# rf-power-detector.net
KiCad netlist of a schematic drawn in EAGLE
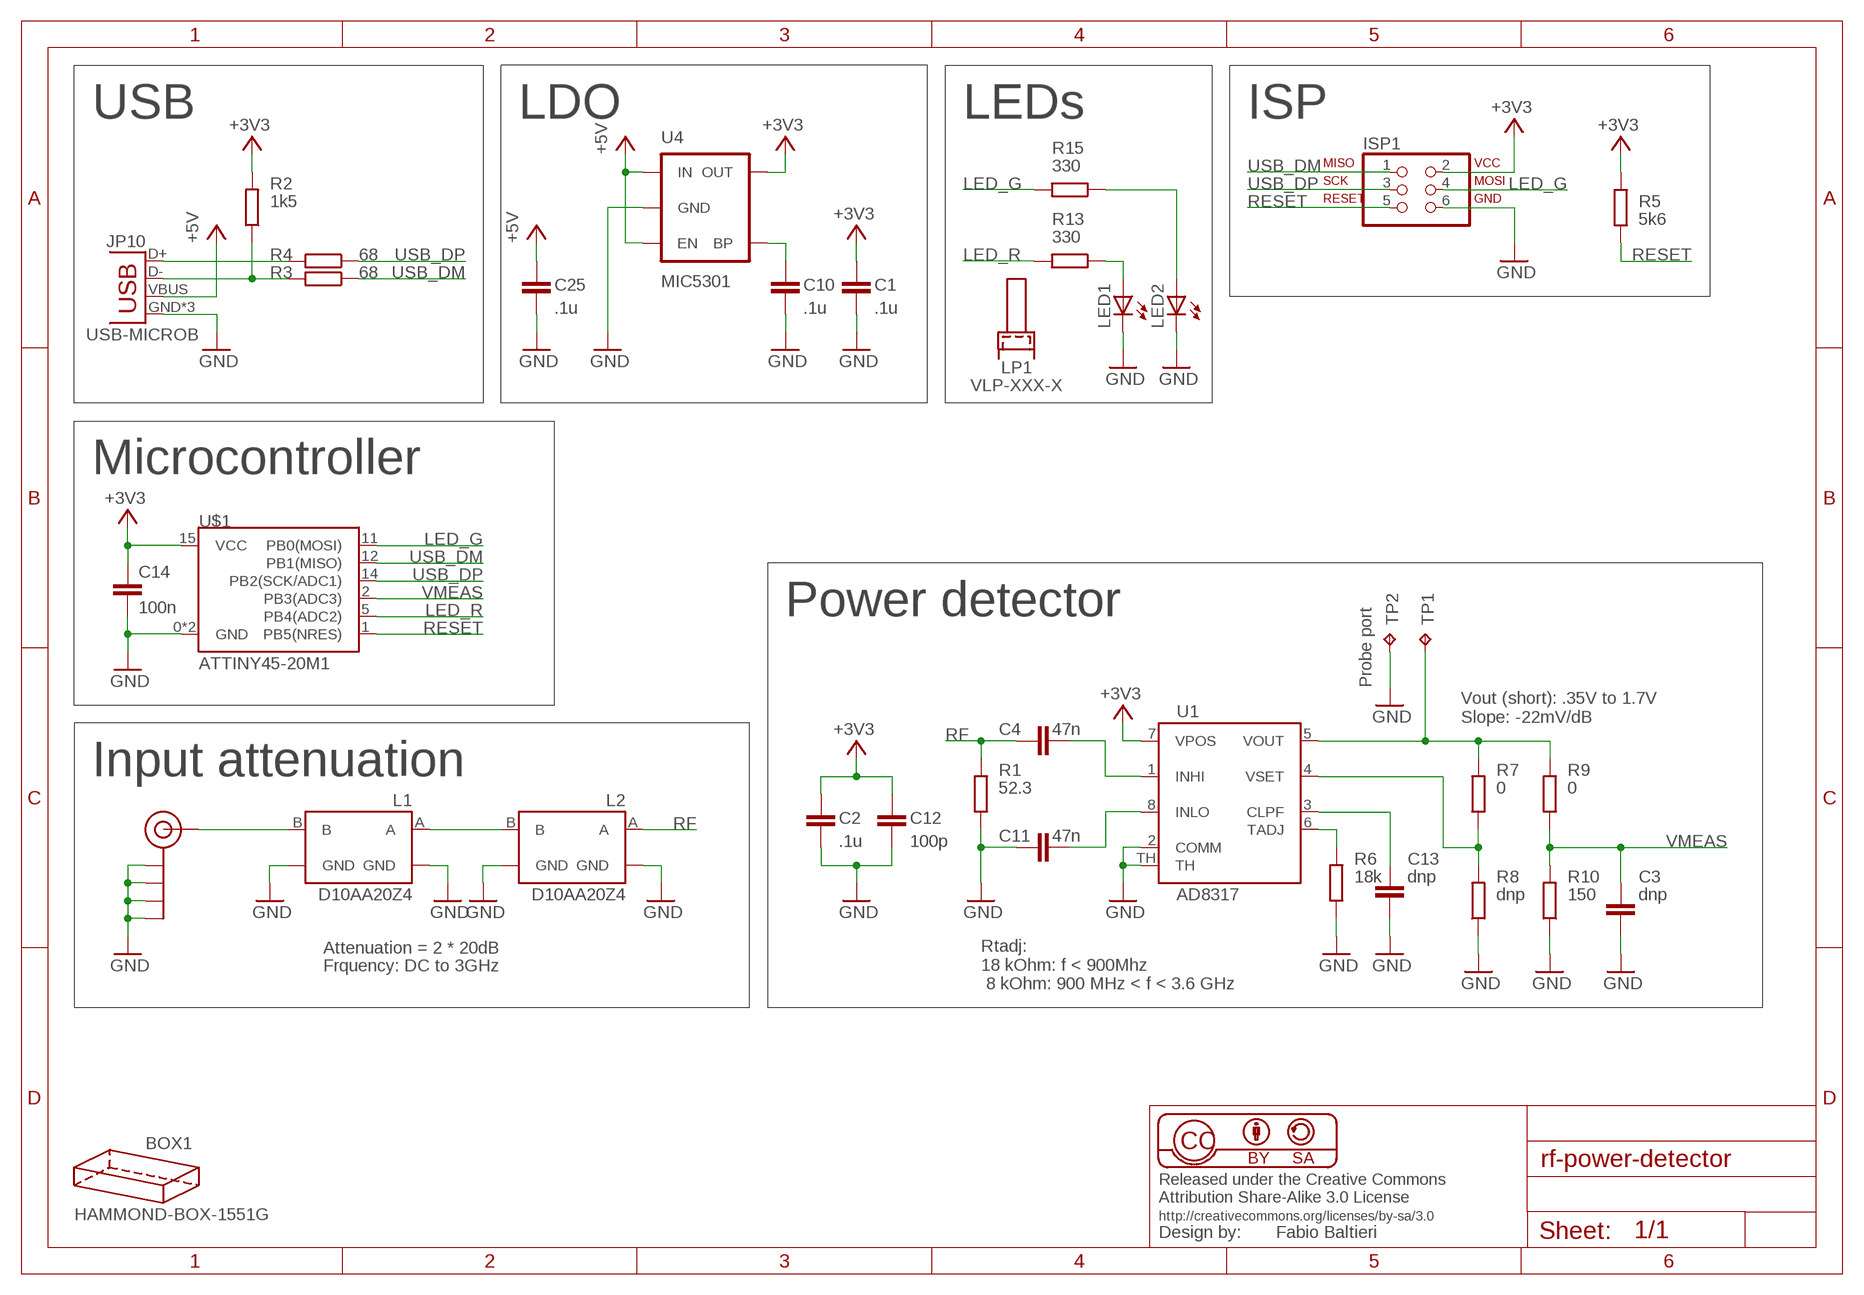
[diagram p0: schematic, sheet 1]

(export (version "E")
  (design (tool "Eeschema 10.0.6"))
  (components
    (comp (ref "BOX1")
      (value "HAMMOND-BOX-1551G")
      (footprint "eagle-import:1551G")
      (libsource (lib "eagle-import") (part "HAMMOND-BOX-1551G"))
    )
    (comp (ref "C1")
      (value ".1u")
      (footprint "eagle-import:C0603")
      (libsource (lib "eagle-import") (part "C-EUC0603"))
    )
    (comp (ref "C2")
      (value ".1u")
      (footprint "eagle-import:C0603")
      (libsource (lib "eagle-import") (part "C-EUC0603"))
    )
    (comp (ref "C3")
      (value "dnp")
      (footprint "eagle-import:C0603")
      (libsource (lib "eagle-import") (part "C-EUC0603"))
    )
    (comp (ref "C4")
      (value "47n")
      (footprint "eagle-import:C0603")
      (libsource (lib "eagle-import") (part "C-EUC0603"))
    )
    (comp (ref "C10")
      (value ".1u")
      (footprint "eagle-import:C0603")
      (libsource (lib "eagle-import") (part "C-EUC0603"))
    )
    (comp (ref "C11")
      (value "47n")
      (footprint "eagle-import:C0603")
      (libsource (lib "eagle-import") (part "C-EUC0603"))
    )
    (comp (ref "C12")
      (value "100p")
      (footprint "eagle-import:C0603")
      (libsource (lib "eagle-import") (part "C-EUC0603"))
    )
    (comp (ref "C13")
      (value "dnp")
      (footprint "eagle-import:C0603")
      (libsource (lib "eagle-import") (part "C-EUC0603"))
    )
    (comp (ref "C14")
      (value "100n")
      (footprint "eagle-import:C0603")
      (libsource (lib "eagle-import") (part "C-EUC0603"))
    )
    (comp (ref "C25")
      (value ".1u")
      (footprint "eagle-import:C0603")
      (libsource (lib "eagle-import") (part "C-EUC0603"))
    )
    (comp (ref "ISP1")
      (value "ISP-AVR910PTH")
      (footprint "eagle-import:2X03")
      (libsource (lib "eagle-import") (part "ISP-AVR910PTH"))
    )
    (comp (ref "J$1")
      (value "SMA_EDGE")
      (footprint "eagle-import:SMA-EDGE")
      (libsource (lib "eagle-import") (part "SMA_EDGE"))
    )
    (comp (ref "JP10")
      (value "USB-MICROB")
      (footprint "eagle-import:USB-MICROB")
      (libsource (lib "eagle-import") (part "USB-MICROB"))
    )
    (comp (ref "L1")
      (value "D10AA20Z4")
      (footprint "eagle-import:D10AAXXZ4")
      (libsource (lib "eagle-import") (part "D10AA20Z4"))
    )
    (comp (ref "L2")
      (value "D10AA20Z4")
      (footprint "eagle-import:D10AAXXZ4")
      (libsource (lib "eagle-import") (part "D10AA20Z4"))
    )
    (comp (ref "LED1")
      (value "LEDSML0805")
      (footprint "eagle-import:SML0805")
      (libsource (lib "eagle-import") (part "LEDSML0805"))
    )
    (comp (ref "LED2")
      (value "LEDSML0805")
      (footprint "eagle-import:SML0805")
      (libsource (lib "eagle-import") (part "LEDSML0805"))
    )
    (comp (ref "LP1")
      (value "VLP-XXX-X")
      (footprint "eagle-import:VLP-XXX-X")
      (libsource (lib "eagle-import") (part "VLP-XXX-X"))
    )
    (comp (ref "R1")
      (value "52.3")
      (footprint "eagle-import:R0603")
      (libsource (lib "eagle-import") (part "R-EU_R0603"))
    )
    (comp (ref "R2")
      (value "1k5")
      (footprint "eagle-import:R0603")
      (libsource (lib "eagle-import") (part "R-EU_R0603"))
    )
    (comp (ref "R3")
      (value "68")
      (footprint "eagle-import:R0603")
      (libsource (lib "eagle-import") (part "R-EU_R0603"))
    )
    (comp (ref "R4")
      (value "68")
      (footprint "eagle-import:R0603")
      (libsource (lib "eagle-import") (part "R-EU_R0603"))
    )
    (comp (ref "R5")
      (value "5k6")
      (footprint "eagle-import:R0603")
      (libsource (lib "eagle-import") (part "R-EU_R0603"))
    )
    (comp (ref "R6")
      (value "18k")
      (footprint "eagle-import:R0603")
      (libsource (lib "eagle-import") (part "R-EU_R0603"))
    )
    (comp (ref "R7")
      (value "0")
      (footprint "eagle-import:R0603")
      (libsource (lib "eagle-import") (part "R-EU_R0603"))
    )
    (comp (ref "R8")
      (value "dnp")
      (footprint "eagle-import:R0603")
      (libsource (lib "eagle-import") (part "R-EU_R0603"))
    )
    (comp (ref "R9")
      (value "0")
      (footprint "eagle-import:R0603")
      (libsource (lib "eagle-import") (part "R-EU_R0603"))
    )
    (comp (ref "R10")
      (value "150")
      (footprint "eagle-import:R0603")
      (libsource (lib "eagle-import") (part "R-EU_R0603"))
    )
    (comp (ref "R13")
      (value "330")
      (footprint "eagle-import:R0603")
      (libsource (lib "eagle-import") (part "R-EU_R0603"))
    )
    (comp (ref "R15")
      (value "330")
      (footprint "eagle-import:R0603")
      (libsource (lib "eagle-import") (part "R-EU_R0603"))
    )
    (comp (ref "TP1")
      (value "TPPAD1-13")
      (footprint "eagle-import:P1-13")
      (libsource (lib "eagle-import") (part "TPPAD1-13"))
    )
    (comp (ref "TP2")
      (value "TPPAD1-13")
      (footprint "eagle-import:P1-13")
      (libsource (lib "eagle-import") (part "TPPAD1-13"))
    )
    (comp (ref "U$1")
      (value "ATTINY45-20M1")
      (footprint "eagle-import:QFN20")
      (libsource (lib "eagle-import") (part "ATTINY45-20M1"))
    )
    (comp (ref "U1")
      (value "AD8317")
      (footprint "eagle-import:LFCSP8")
      (libsource (lib "eagle-import") (part "AD8317"))
    )
    (comp (ref "U4")
      (value "MIC5301")
      (footprint "eagle-import:SOT23-5")
      (libsource (lib "eagle-import") (part "V_REG_LDOSMD"))
    )
  )
  (nets
    (net (code "1") (name "+3V3") (class "Default")
      (node (ref "C1") (pin "1") (pinfunction "1_1") (pintype "passive"))
      (node (ref "C12") (pin "1") (pinfunction "1_1") (pintype "passive"))
      (node (ref "C14") (pin "1") (pinfunction "1_1") (pintype "passive"))
      (node (ref "C2") (pin "1") (pinfunction "1_1") (pintype "passive"))
      (node (ref "ISP1") (pin "2") (pinfunction "2_2") (pintype "passive"))
      (node (ref "R2") (pin "2") (pinfunction "2_2") (pintype "passive"))
      (node (ref "R5") (pin "1") (pinfunction "1_1") (pintype "passive"))
      (node (ref "U$1") (pin "15") (pinfunction "VCC_15") (pintype "bidirectional"))
      (node (ref "U1") (pin "7") (pinfunction "VPOS_7") (pintype "bidirectional"))
      (node (ref "U4") (pin "5") (pinfunction "OUT_5") (pintype "passive"))
    )
    (net (code "2") (name "+5V") (class "Default")
      (node (ref "C25") (pin "1") (pinfunction "1_1") (pintype "passive"))
      (node (ref "JP10") (pin "VBUS") (pinfunction "VBUS_VBUS") (pintype "bidirectional"))
      (node (ref "U4") (pin "1") (pinfunction "IN_1") (pintype "input"))
      (node (ref "U4") (pin "3") (pinfunction "EN_3") (pintype "input"))
    )
    (net (code "3") (name "/LED_G") (class "Default")
      (node (ref "ISP1") (pin "4") (pinfunction "4_4") (pintype "passive"))
      (node (ref "R15") (pin "2") (pinfunction "2_2") (pintype "passive"))
      (node (ref "U$1") (pin "11") (pinfunction "PB0(MOSI)_11") (pintype "bidirectional"))
    )
    (net (code "4") (name "/LED_R") (class "Default")
      (node (ref "R13") (pin "2") (pinfunction "2_2") (pintype "passive"))
      (node (ref "U$1") (pin "5") (pinfunction "PB4(ADC2)_5") (pintype "bidirectional"))
    )
    (net (code "5") (name "/RESET") (class "Default")
      (node (ref "ISP1") (pin "5") (pinfunction "5_5") (pintype "passive"))
      (node (ref "R5") (pin "2") (pinfunction "2_2") (pintype "passive"))
      (node (ref "U$1") (pin "1") (pinfunction "PB5(NRES)_1") (pintype "bidirectional"))
    )
    (net (code "6") (name "/RF") (class "Default")
      (node (ref "C4") (pin "1") (pinfunction "1_1") (pintype "passive"))
      (node (ref "L2") (pin "A") (pinfunction "A_A") (pintype "bidirectional"))
      (node (ref "R1") (pin "2") (pinfunction "2_2") (pintype "passive"))
    )
    (net (code "7") (name "/USB_DM") (class "Default")
      (node (ref "ISP1") (pin "1") (pinfunction "1_1") (pintype "passive"))
      (node (ref "R3") (pin "1") (pinfunction "1_1") (pintype "passive"))
      (node (ref "U$1") (pin "12") (pinfunction "PB1(MISO)_12") (pintype "bidirectional"))
    )
    (net (code "8") (name "/USB_DP") (class "Default")
      (node (ref "ISP1") (pin "3") (pinfunction "3_3") (pintype "passive"))
      (node (ref "R4") (pin "1") (pinfunction "1_1") (pintype "passive"))
      (node (ref "U$1") (pin "14") (pinfunction "PB2(SCK/ADC1)_14") (pintype "bidirectional"))
    )
    (net (code "9") (name "/VMEAS") (class "Default")
      (node (ref "C3") (pin "1") (pinfunction "1_1") (pintype "passive"))
      (node (ref "R10") (pin "2") (pinfunction "2_2") (pintype "passive"))
      (node (ref "R9") (pin "1") (pinfunction "1_1") (pintype "passive"))
      (node (ref "U$1") (pin "2") (pinfunction "PB3(ADC3)_2") (pintype "bidirectional"))
    )
    (net (code "10") (name "GND") (class "Default")
      (node (ref "C1") (pin "2") (pinfunction "2_2") (pintype "passive"))
      (node (ref "C10") (pin "2") (pinfunction "2_2") (pintype "passive"))
      (node (ref "C11") (pin "1") (pinfunction "1_1") (pintype "passive"))
      (node (ref "C12") (pin "2") (pinfunction "2_2") (pintype "passive"))
      (node (ref "C13") (pin "2") (pinfunction "2_2") (pintype "passive"))
      (node (ref "C14") (pin "2") (pinfunction "2_2") (pintype "passive"))
      (node (ref "C2") (pin "2") (pinfunction "2_2") (pintype "passive"))
      (node (ref "C25") (pin "2") (pinfunction "2_2") (pintype "passive"))
      (node (ref "C3") (pin "2") (pinfunction "2_2") (pintype "passive"))
      (node (ref "ISP1") (pin "6") (pinfunction "6_6") (pintype "passive"))
      (node (ref "J$1") (pin "GND@0") (pinfunction "GND_GND@0") (pintype "bidirectional"))
      (node (ref "J$1") (pin "GND@1") (pinfunction "GND_GND@1") (pintype "bidirectional"))
      (node (ref "J$1") (pin "GND@2") (pinfunction "GND_GND@2") (pintype "bidirectional"))
      (node (ref "J$1") (pin "GND@3") (pinfunction "GND_GND@3") (pintype "bidirectional"))
      (node (ref "JP10") (pin "GND") (pinfunction "GND_GND") (pintype "bidirectional"))
      (node (ref "JP10") (pin "MT1") (pinfunction "GND_MT1") (pintype "bidirectional"))
      (node (ref "JP10") (pin "MT2") (pinfunction "GND_MT2") (pintype "bidirectional"))
      (node (ref "L1") (pin "GND@0") (pinfunction "GND_GND@0") (pintype "bidirectional"))
      (node (ref "L1") (pin "GND@1") (pinfunction "GND_GND@1") (pintype "bidirectional"))
      (node (ref "L2") (pin "GND@0") (pinfunction "GND_GND@0") (pintype "bidirectional"))
      (node (ref "L2") (pin "GND@1") (pinfunction "GND_GND@1") (pintype "bidirectional"))
      (node (ref "LED1") (pin "C") (pinfunction "C_C") (pintype "passive"))
      (node (ref "LED2") (pin "C") (pinfunction "C_C") (pintype "passive"))
      (node (ref "R1") (pin "1") (pinfunction "1_1") (pintype "passive"))
      (node (ref "R10") (pin "1") (pinfunction "1_1") (pintype "passive"))
      (node (ref "R6") (pin "1") (pinfunction "1_1") (pintype "passive"))
      (node (ref "R8") (pin "1") (pinfunction "1_1") (pintype "passive"))
      (node (ref "TP2") (pin "TP") (pinfunction "TP_TP") (pintype "input"))
      (node (ref "U$1") (pin "0") (pinfunction "GND_0") (pintype "bidirectional"))
      (node (ref "U$1") (pin "8") (pinfunction "GND_8") (pintype "bidirectional"))
      (node (ref "U1") (pin "2") (pinfunction "COMM_2") (pintype "bidirectional"))
      (node (ref "U1") (pin "TH") (pinfunction "TH_TH") (pintype "bidirectional"))
      (node (ref "U4") (pin "2") (pinfunction "GND_2") (pintype "input"))
    )
    (net (code "11") (name "Net-(J$1-SIGNAL)") (class "Default")
      (node (ref "J$1") (pin "SIG") (pinfunction "SIGNAL_SIG") (pintype "bidirectional"))
      (node (ref "L1") (pin "B") (pinfunction "B_B") (pintype "bidirectional"))
    )
    (net (code "12") (name "Net-(JP10-PadD+)") (class "Default")
      (node (ref "JP10") (pin "D+") (pinfunction "D+_D+") (pintype "bidirectional"))
      (node (ref "R4") (pin "2") (pinfunction "2_2") (pintype "passive"))
    )
    (net (code "13") (name "Net-(JP10-PadD-)") (class "Default")
      (node (ref "JP10") (pin "D-") (pinfunction "D-_D-") (pintype "bidirectional"))
      (node (ref "R2") (pin "1") (pinfunction "1_1") (pintype "passive"))
      (node (ref "R3") (pin "2") (pinfunction "2_2") (pintype "passive"))
    )
    (net (code "14") (name "Net-(L1-PadA)") (class "Default")
      (node (ref "L1") (pin "A") (pinfunction "A_A") (pintype "bidirectional"))
      (node (ref "L2") (pin "B") (pinfunction "B_B") (pintype "bidirectional"))
    )
    (net (code "15") (name "Net-(LED1-PadA)") (class "Default")
      (node (ref "LED1") (pin "A") (pinfunction "A_A") (pintype "passive"))
      (node (ref "R13") (pin "1") (pinfunction "1_1") (pintype "passive"))
    )
    (net (code "16") (name "Net-(LED2-PadA)") (class "Default")
      (node (ref "LED2") (pin "A") (pinfunction "A_A") (pintype "passive"))
      (node (ref "R15") (pin "1") (pinfunction "1_1") (pintype "passive"))
    )
    (net (code "17") (name "Net-(U1-CLPF)") (class "Default")
      (node (ref "C13") (pin "1") (pinfunction "1_1") (pintype "passive"))
      (node (ref "U1") (pin "3") (pinfunction "CLPF_3") (pintype "bidirectional"))
    )
    (net (code "18") (name "Net-(U1-INHI)") (class "Default")
      (node (ref "C4") (pin "2") (pinfunction "2_2") (pintype "passive"))
      (node (ref "U1") (pin "1") (pinfunction "INHI_1") (pintype "bidirectional"))
    )
    (net (code "19") (name "Net-(U1-INLO)") (class "Default")
      (node (ref "C11") (pin "2") (pinfunction "2_2") (pintype "passive"))
      (node (ref "U1") (pin "8") (pinfunction "INLO_8") (pintype "bidirectional"))
    )
    (net (code "20") (name "Net-(U1-TADJ)") (class "Default")
      (node (ref "R6") (pin "2") (pinfunction "2_2") (pintype "passive"))
      (node (ref "U1") (pin "6") (pinfunction "TADJ_6") (pintype "bidirectional"))
    )
    (net (code "21") (name "Net-(U1-VOUT)") (class "Default")
      (node (ref "R7") (pin "2") (pinfunction "2_2") (pintype "passive"))
      (node (ref "R9") (pin "2") (pinfunction "2_2") (pintype "passive"))
      (node (ref "TP1") (pin "TP") (pinfunction "TP_TP") (pintype "input"))
      (node (ref "U1") (pin "5") (pinfunction "VOUT_5") (pintype "bidirectional"))
    )
    (net (code "22") (name "Net-(U1-VSET)") (class "Default")
      (node (ref "R7") (pin "1") (pinfunction "1_1") (pintype "passive"))
      (node (ref "R8") (pin "2") (pinfunction "2_2") (pintype "passive"))
      (node (ref "U1") (pin "4") (pinfunction "VSET_4") (pintype "bidirectional"))
    )
    (net (code "23") (name "Net-(U4-BP)") (class "Default")
      (node (ref "C10") (pin "1") (pinfunction "1_1") (pintype "passive"))
      (node (ref "U4") (pin "4") (pinfunction "BP_4") (pintype "input"))
    )
  )
)
